# estop_circuitry.net
KiCad netlist of a schematic drawn in Altium Designer
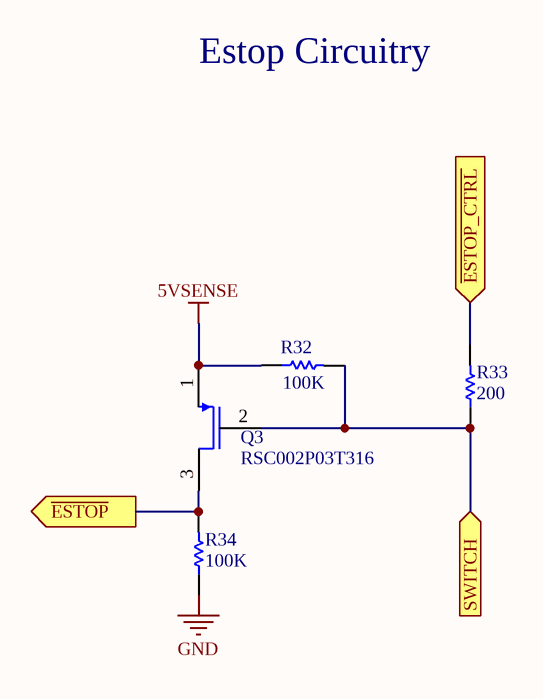
[diagram p0: estop_circuitry.SchDoc]

(export (version "E")
  (design (tool "Eeschema 10.0.6"))
  (components
    (comp (ref "Q3")
      (value "RSC002P03T316")
      (footprint "SOT-23")
      (description "MOSFET P-CH 30V 0.25A SST3")
      (fields (field (name "MANUFACTURER") "Rohm Semiconductor"))
      (libsource (lib "common") (part "RSC002P03T316"))
    )
    (comp (ref "R32")
      (value "100K")
      (footprint "RESC1608N")
      (description "Resistor")
      (fields
        (field (name "MANUFACTURER") "Yageo")
        (field (name "MANUFACTURER PART NUMBER") "RC0603JR-07100KL")
        (field (name "PUBLISHER") "Altium Limited")
      )
      (libsource (lib "Miscellaneous Devices") (part "Res1"))
    )
    (comp (ref "R33")
      (value "200")
      (footprint "RESC1608N")
      (description "Resistor")
      (fields
        (field (name "MANUFACTURER") "Yageo")
        (field (name "MANUFACTURER PART NUMBER") "RC0603JR-07200RL")
        (field (name "PUBLISHER") "Altium Limited")
      )
      (libsource (lib "Miscellaneous Devices") (part "Res1"))
    )
    (comp (ref "R34")
      (value "100K")
      (footprint "RESC1608N")
      (description "Resistor")
      (fields
        (field (name "MANUFACTURER") "Yageo")
        (field (name "MANUFACTURER PART NUMBER") "RC0603JR-07100KL")
        (field (name "PUBLISHER") "Altium Limited")
      )
      (libsource (lib "Miscellaneous Devices") (part "Res1"))
    )
  )
  (nets
    (net (code "1") (name "/SWITCH") (class "Default")
      (node (ref "Q3") (pin "2") (pinfunction "2_2") (pintype "passive"))
      (node (ref "R32") (pin "2") (pinfunction "2_2") (pintype "passive"))
      (node (ref "R33") (pin "1") (pinfunction "1_1") (pintype "passive"))
    )
    (net (code "2") (name "/~{ESTOP_CTRL}") (class "Default")
      (node (ref "R33") (pin "2") (pinfunction "2_2") (pintype "passive"))
    )
    (net (code "3") (name "/~{ESTOP}") (class "Default")
      (node (ref "Q3") (pin "3") (pinfunction "3_3") (pintype "passive"))
      (node (ref "R34") (pin "2") (pinfunction "2_2") (pintype "passive"))
    )
    (net (code "4") (name "5VSENSE") (class "Default")
      (node (ref "Q3") (pin "1") (pinfunction "1_1") (pintype "passive"))
      (node (ref "R32") (pin "1") (pinfunction "1_1") (pintype "passive"))
    )
    (net (code "5") (name "GND") (class "Default")
      (node (ref "R34") (pin "1") (pinfunction "1_1") (pintype "passive"))
    )
  )
)
